# Guide_laser.net
KiCad netlist of a schematic drawn in Altium Designer
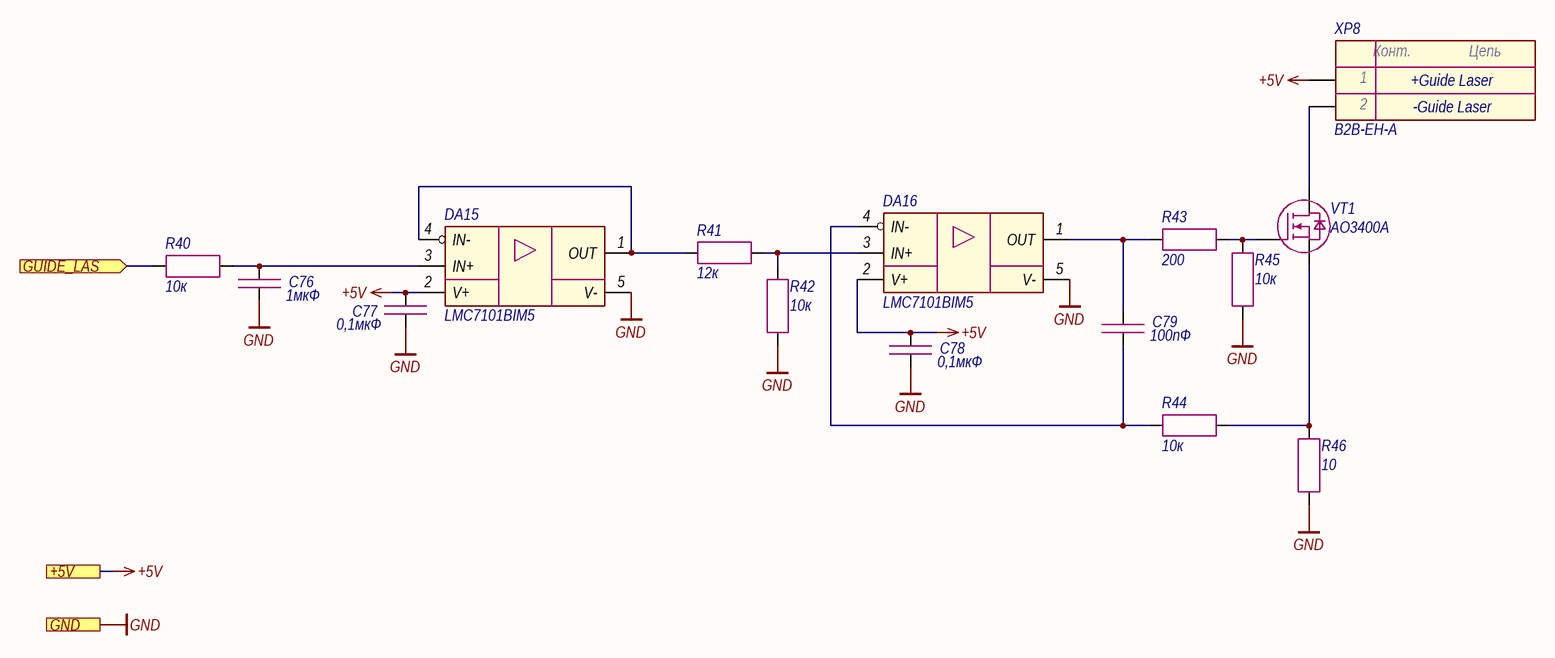
[diagram p0: Guide_laser.SchDoc]

(export (version "E")
  (design (tool "Eeschema 10.0.6"))
  (components
    (comp (ref "C76")
      (value "1мкФ")
      (footprint "Pcb_library:CAP_0603")
      (fields (field (name "MANUFACTURER") "Murata"))
      (libsource (lib "Schem_library") (part "Capacitor"))
    )
    (comp (ref "C77")
      (value "0,1мкФ")
      (footprint "Pcb_library:CAP_0603")
      (fields (field (name "MANUFACTURER") "Murata"))
      (libsource (lib "Schem_library") (part "Capacitor"))
    )
    (comp (ref "C78")
      (value "0,1мкФ")
      (footprint "Pcb_library:CAP_0603")
      (fields (field (name "MANUFACTURER") "Murata"))
      (libsource (lib "Schem_library") (part "Capacitor"))
    )
    (comp (ref "C79")
      (value "100пФ")
      (footprint "Pcb_library:CAP_0603")
      (fields (field (name "MANUFACTURER") "Murata"))
      (libsource (lib "Schem_library") (part "Capacitor"))
    )
    (comp (ref "DA15")
      (value "LMC7101BIM5")
      (footprint "Pcb_library:SOT-23-5")
      (fields (field (name "MANUFACTURER") "Texas Instruments"))
      (libsource (lib "Schem_library") (part "LMC7101"))
    )
    (comp (ref "DA16")
      (value "LMC7101BIM5")
      (footprint "Pcb_library:SOT-23-5")
      (fields (field (name "MANUFACTURER") "Texas Instruments"))
      (libsource (lib "Schem_library") (part "LMC7101"))
    )
    (comp (ref "R40")
      (value "10к")
      (footprint "Pcb_library:RES_0603")
      (fields (field (name "MANUFACTURER") "Yageo"))
      (libsource (lib "Schem_library") (part "Resistor"))
    )
    (comp (ref "R41")
      (value "12к")
      (footprint "Pcb_library:RES_0603")
      (fields (field (name "MANUFACTURER") "Yageo"))
      (libsource (lib "Schem_library") (part "Resistor"))
    )
    (comp (ref "R42")
      (value "10к")
      (footprint "Pcb_library:RES_0603")
      (fields (field (name "MANUFACTURER") "Yageo"))
      (libsource (lib "Schem_library") (part "Resistor"))
    )
    (comp (ref "R43")
      (value "200")
      (footprint "Pcb_library:RES_0603")
      (fields (field (name "MANUFACTURER") "Yageo"))
      (libsource (lib "Schem_library") (part "Resistor"))
    )
    (comp (ref "R44")
      (value "10к")
      (footprint "Pcb_library:RES_0603")
      (fields (field (name "MANUFACTURER") "Yageo"))
      (libsource (lib "Schem_library") (part "Resistor"))
    )
    (comp (ref "R45")
      (value "10к")
      (footprint "Pcb_library:RES_0603")
      (fields (field (name "MANUFACTURER") "Yageo"))
      (libsource (lib "Schem_library") (part "Resistor"))
    )
    (comp (ref "R46")
      (value "10")
      (footprint "Pcb_library:RES_1210")
      (fields (field (name "MANUFACTURER") "Yageo"))
      (libsource (lib "Schem_library") (part "Resistor"))
    )
    (comp (ref "VT1")
      (value "AO3400A")
      (footprint "Pcb_library:SOT-23-3")
      (fields (field (name "MANUFACTURER") "UMW"))
      (libsource (lib "Schem_library") (part "MOSFET N-channel"))
    )
    (comp (ref "XP8")
      (value "B2B-EH-A")
      (footprint "Pcb_library:B2B-EH-A")
      (fields (field (name "MANUFACTURER") "JST"))
      (libsource (lib "Schem_library") (part "Connector-2"))
    )
  )
  (nets
    (net (code "1") (name "+5V") (class "Default")
      (node (ref "C77") (pin "1") (pinfunction "1_1") (pintype "passive"))
      (node (ref "C78") (pin "1") (pinfunction "1_1") (pintype "passive"))
      (node (ref "DA15") (pin "2") (pinfunction "V+_2") (pintype "passive"))
      (node (ref "DA16") (pin "2") (pinfunction "V+_2") (pintype "passive"))
      (node (ref "XP8") (pin "1") (pintype "passive"))
    )
    (net (code "2") (name "/GUIDE_LAS") (class "Default")
      (node (ref "R40") (pin "1") (pinfunction "1_1") (pintype "passive"))
    )
    (net (code "3") (name "GND") (class "Default")
      (node (ref "C76") (pin "2") (pinfunction "2_2") (pintype "passive"))
      (node (ref "C77") (pin "2") (pinfunction "2_2") (pintype "passive"))
      (node (ref "C78") (pin "2") (pinfunction "2_2") (pintype "passive"))
      (node (ref "DA15") (pin "5") (pinfunction "V-_5") (pintype "passive"))
      (node (ref "DA16") (pin "5") (pinfunction "V-_5") (pintype "passive"))
      (node (ref "R42") (pin "2") (pinfunction "2_2") (pintype "passive"))
      (node (ref "R45") (pin "1") (pinfunction "1_1") (pintype "passive"))
      (node (ref "R46") (pin "1") (pinfunction "1_1") (pintype "passive"))
    )
    (net (code "4") (name "Net-(DA15-IN+)") (class "Default")
      (node (ref "C76") (pin "1") (pinfunction "1_1") (pintype "passive"))
      (node (ref "DA15") (pin "3") (pinfunction "IN+_3") (pintype "passive"))
      (node (ref "R40") (pin "2") (pinfunction "2_2") (pintype "passive"))
    )
    (net (code "5") (name "Net-(DA15-IN-)") (class "Default")
      (node (ref "DA15") (pin "1") (pinfunction "OUT_1") (pintype "passive"))
      (node (ref "DA15") (pin "4") (pinfunction "IN-_4") (pintype "passive"))
      (node (ref "R41") (pin "1") (pinfunction "1_1") (pintype "passive"))
    )
    (net (code "6") (name "Net-(DA16-IN+)") (class "Default")
      (node (ref "DA16") (pin "3") (pinfunction "IN+_3") (pintype "passive"))
      (node (ref "R41") (pin "2") (pinfunction "2_2") (pintype "passive"))
      (node (ref "R42") (pin "1") (pinfunction "1_1") (pintype "passive"))
    )
    (net (code "7") (name "Net-(DA16-IN-)") (class "Default")
      (node (ref "C79") (pin "2") (pinfunction "2_2") (pintype "passive"))
      (node (ref "DA16") (pin "4") (pinfunction "IN-_4") (pintype "passive"))
      (node (ref "R44") (pin "1") (pinfunction "1_1") (pintype "passive"))
    )
    (net (code "8") (name "Net-(DA16-OUT)") (class "Default")
      (node (ref "C79") (pin "1") (pinfunction "1_1") (pintype "passive"))
      (node (ref "DA16") (pin "1") (pinfunction "OUT_1") (pintype "passive"))
      (node (ref "R43") (pin "1") (pinfunction "1_1") (pintype "passive"))
    )
    (net (code "9") (name "Net-(VT1-D)") (class "Default")
      (node (ref "VT1") (pin "3") (pinfunction "D_3") (pintype "passive"))
      (node (ref "XP8") (pin "2") (pintype "passive"))
    )
    (net (code "10") (name "Net-(VT1-G)") (class "Default")
      (node (ref "R43") (pin "2") (pinfunction "2_2") (pintype "passive"))
      (node (ref "R45") (pin "2") (pinfunction "2_2") (pintype "passive"))
      (node (ref "VT1") (pin "1") (pinfunction "G_1") (pintype "passive"))
    )
    (net (code "11") (name "Net-(VT1-S)") (class "Default")
      (node (ref "R44") (pin "2") (pinfunction "2_2") (pintype "passive"))
      (node (ref "R46") (pin "2") (pinfunction "2_2") (pintype "passive"))
      (node (ref "VT1") (pin "2") (pinfunction "S_2") (pintype "passive"))
    )
  )
)
